# CAN.net
KiCad netlist of a schematic drawn in Altium Designer
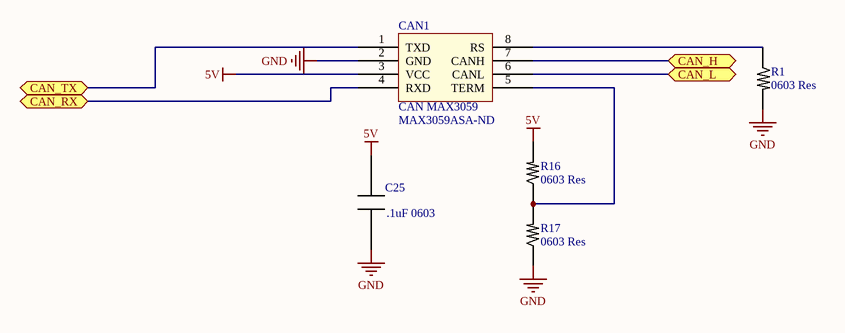
[diagram p0: CAN.SchDoc]

(export (version "E")
  (design (tool "Eeschema 10.0.6"))
  (components
    (comp (ref "C25")
      (value ".1uF 0603")
      (footprint "0603/1608 SMD Resistor")
      (libsource (lib "CornellBajaLibrary") (part "0603 Cap"))
    )
    (comp (ref "CAN1")
      (value "CAN MAX3059")
      (footprint "TJA1040")
      (fields (field (name "SUPPLIER PART NUMBER 1") "MAX3059ASA-ND"))
      (libsource (lib "CornellBajaLibrary") (part "CAN MAX3059"))
    )
    (comp (ref "R1")
      (value "0603 Res")
      (footprint "0603/1608 SMD Resistor")
      (libsource (lib "CornellBajaLibrary") (part "0603 Res"))
    )
    (comp (ref "R16")
      (value "0603 Res")
      (footprint "0603/1608 SMD Resistor")
      (libsource (lib "BajaIntegrated") (part "0603 Res"))
    )
    (comp (ref "R17")
      (value "0603 Res")
      (footprint "0603/1608 SMD Resistor")
      (libsource (lib "BajaIntegrated") (part "0603 Res"))
    )
  )
  (nets
    (net (code "1") (name "/CAN_H") (class "Default")
      (node (ref "CAN1") (pin "7") (pinfunction "CANH_7") (pintype "passive"))
    )
    (net (code "2") (name "/CAN_L") (class "Default")
      (node (ref "CAN1") (pin "6") (pinfunction "CANL_6") (pintype "passive"))
    )
    (net (code "3") (name "/CAN_RX") (class "Default")
      (node (ref "CAN1") (pin "4") (pinfunction "RXD_4") (pintype "passive"))
    )
    (net (code "4") (name "/CAN_TX") (class "Default")
      (node (ref "CAN1") (pin "1") (pinfunction "TXD_1") (pintype "passive"))
    )
    (net (code "5") (name "5V") (class "Default")
      (node (ref "C25") (pin "2") (pinfunction "2_2") (pintype "passive"))
      (node (ref "CAN1") (pin "3") (pinfunction "VCC_3") (pintype "passive"))
      (node (ref "R16") (pin "2") (pinfunction "2_2") (pintype "passive"))
    )
    (net (code "6") (name "GND") (class "Default")
      (node (ref "C25") (pin "1") (pinfunction "1_1") (pintype "passive"))
      (node (ref "CAN1") (pin "2") (pinfunction "GND_2") (pintype "passive"))
      (node (ref "R1") (pin "2") (pinfunction "2_2") (pintype "passive"))
      (node (ref "R17") (pin "1") (pinfunction "1_1") (pintype "passive"))
    )
    (net (code "7") (name "Net-(CAN1-RS)") (class "Default")
      (node (ref "CAN1") (pin "8") (pinfunction "RS_8") (pintype "passive"))
      (node (ref "R1") (pin "1") (pinfunction "1_1") (pintype "passive"))
    )
    (net (code "8") (name "Net-(CAN1-TERM)") (class "Default")
      (node (ref "CAN1") (pin "5") (pinfunction "TERM_5") (pintype "passive"))
      (node (ref "R16") (pin "1") (pinfunction "1_1") (pintype "passive"))
      (node (ref "R17") (pin "2") (pinfunction "2_2") (pintype "passive"))
    )
  )
)
